# Breakout.net
KiCad netlist of a schematic drawn in Altium Designer
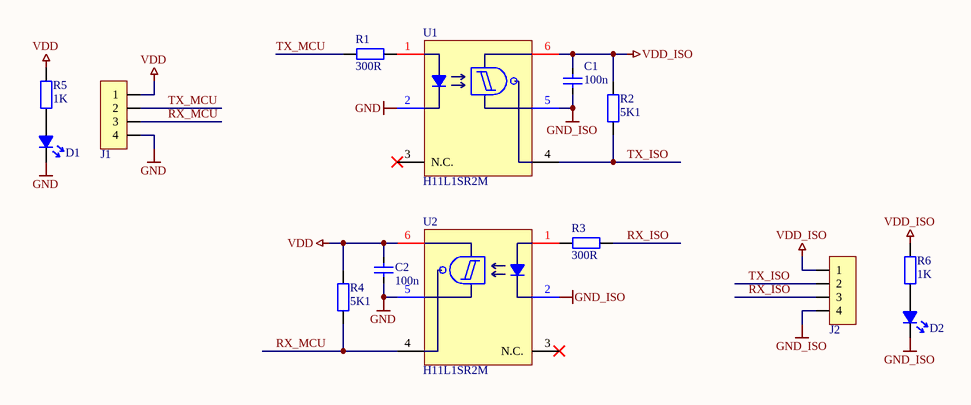
[diagram p0: Breakout.SchDoc]

(export (version "E")
  (design (tool "Eeschema 10.0.6"))
  (components
    (comp (ref "C1")
      (value "100n")
      (footprint "0805C_RF_M")
      (description "Capacitor")
      (fields (field (name "TOLERANCE") "?") (field (name "MANUFACTURER") "Generic Brand"))
      (libsource (lib "AG.Generic") (part "C"))
    )
    (comp (ref "C2")
      (value "100n")
      (footprint "0805C_RF_M")
      (description "Capacitor")
      (fields (field (name "TOLERANCE") "?") (field (name "MANUFACTURER") "Generic Brand"))
      (libsource (lib "AG.Generic") (part "C"))
    )
    (comp (ref "D1")
      (value "Unspecified")
      (footprint "0805LED_RF_M")
      (description "LED")
      (fields (field (name "MANUFACTURER") "Generic Brand"))
      (libsource (lib "AG.Generic") (part "LED"))
    )
    (comp (ref "D2")
      (value "Unspecified")
      (footprint "0805LED_RF_M")
      (description "LED")
      (fields (field (name "MANUFACTURER") "Generic Brand"))
      (libsource (lib "AG.Generic") (part "LED"))
    )
    (comp (ref "J1")
      (value "PINHDR-4P1")
      (footprint "AG.Connectors:HEADER-2.54-4P1")
      (description "Generic Pin Header 4x1")
      (libsource (lib "") (part "PINHDR-4P1_1"))
    )
    (comp (ref "J2")
      (value "PINHDR-4P1")
      (footprint "AG.Connectors:HEADER-2.54-4P1")
      (description "Generic Pin Header 4x1")
      (libsource (lib "AG.Connectors") (part "PINHDR-4P1"))
    )
    (comp (ref "R1")
      (value "300R")
      (footprint "0805R_RF_M")
      (description "Resistor")
      (fields (field (name "TOLERANCE") "?") (field (name "MANUFACTURER") "Generic Brand"))
      (libsource (lib "AG.Generic") (part "R"))
    )
    (comp (ref "R2")
      (value "5K1")
      (footprint "0805R_RF_M")
      (description "Resistor")
      (fields (field (name "TOLERANCE") "?") (field (name "MANUFACTURER") "Generic Brand"))
      (libsource (lib "AG.Generic") (part "R"))
    )
    (comp (ref "R3")
      (value "300R")
      (footprint "0805R_RF_M")
      (description "Resistor")
      (fields (field (name "TOLERANCE") "?") (field (name "MANUFACTURER") "Generic Brand"))
      (libsource (lib "AG.Generic") (part "R"))
    )
    (comp (ref "R4")
      (value "5K1")
      (footprint "0805R_RF_M")
      (description "Resistor")
      (fields (field (name "TOLERANCE") "?") (field (name "MANUFACTURER") "Generic Brand"))
      (libsource (lib "AG.Generic") (part "R"))
    )
    (comp (ref "R5")
      (value "1K")
      (footprint "0805R_RF_M")
      (description "Resistor")
      (fields (field (name "TOLERANCE") "?") (field (name "MANUFACTURER") "Generic Brand"))
      (libsource (lib "AG.Generic") (part "R"))
    )
    (comp (ref "R6")
      (value "1K")
      (footprint "0805R_RF_M")
      (description "Resistor")
      (fields (field (name "TOLERANCE") "?") (field (name "MANUFACTURER") "Generic Brand"))
      (libsource (lib "AG.Generic") (part "R"))
    )
    (comp (ref "U1")
      (value "H11L1SR2M")
      (footprint "AG.IC:H11L1SR2M_SMD-6")
      (description "OPTOISO 4.17KV OPN COLL SMD-6")
      (fields
        (field (name "MANUFACTURER") "ON Semiconductor")
        (field (name "ALTERNATIVE SUPPLIER PART NO") "753715628")
      )
      (libsource (lib "") (part "H11L1SR2M_1"))
    )
    (comp (ref "U2")
      (value "H11L1SR2M")
      (footprint "AG.IC:H11L1SR2M_SMD-6")
      (description "OPTOISO 4.17KV OPN COLL SMD-6")
      (fields
        (field (name "MANUFACTURER") "ON Semiconductor")
        (field (name "ALTERNATIVE SUPPLIER PART NO") "753715628")
      )
      (libsource (lib "AG.Discrete") (part "H11L1SR2M"))
    )
  )
  (nets
    (net (code "1") (name "/RX_ISO") (class "Default")
      (node (ref "J2") (pin "3") (pinfunction "3_3") (pintype "passive"))
      (node (ref "R3") (pin "2") (pintype "passive"))
    )
    (net (code "2") (name "/RX_MCU") (class "Default")
      (node (ref "J1") (pin "3") (pinfunction "3_3") (pintype "passive"))
      (node (ref "R4") (pin "1") (pintype "passive"))
      (node (ref "U2") (pin "4") (pinfunction "OUT_4") (pintype "passive"))
    )
    (net (code "3") (name "/TX_ISO") (class "Default")
      (node (ref "J2") (pin "2") (pinfunction "2_2") (pintype "passive"))
      (node (ref "R2") (pin "1") (pintype "passive"))
      (node (ref "U1") (pin "4") (pinfunction "OUT_4") (pintype "passive"))
    )
    (net (code "4") (name "/TX_MCU") (class "Default")
      (node (ref "J1") (pin "2") (pinfunction "2_2") (pintype "passive"))
      (node (ref "R1") (pin "1") (pintype "passive"))
    )
    (net (code "5") (name "GND") (class "Default")
      (node (ref "C2") (pin "1") (pinfunction "1_1") (pintype "passive"))
      (node (ref "D1") (pin "C") (pinfunction "C_C") (pintype "passive"))
      (node (ref "J1") (pin "4") (pinfunction "4_4") (pintype "passive"))
      (node (ref "U1") (pin "2") (pinfunction "C_2") (pintype "passive"))
      (node (ref "U2") (pin "5") (pinfunction "GND_5") (pintype "power_in"))
    )
    (net (code "6") (name "GND_ISO") (class "Default")
      (node (ref "C1") (pin "1") (pinfunction "1_1") (pintype "passive"))
      (node (ref "D2") (pin "C") (pinfunction "C_C") (pintype "passive"))
      (node (ref "J2") (pin "4") (pinfunction "4_4") (pintype "passive"))
      (node (ref "U1") (pin "5") (pinfunction "GND_5") (pintype "power_in"))
      (node (ref "U2") (pin "2") (pinfunction "C_2") (pintype "passive"))
    )
    (net (code "7") (name "Net-(D1-PadA)") (class "Default")
      (node (ref "D1") (pin "A") (pinfunction "A_A") (pintype "passive"))
      (node (ref "R5") (pin "1") (pintype "passive"))
    )
    (net (code "8") (name "Net-(D2-PadA)") (class "Default")
      (node (ref "D2") (pin "A") (pinfunction "A_A") (pintype "passive"))
      (node (ref "R6") (pin "1") (pintype "passive"))
    )
    (net (code "9") (name "Net-(U1-A)") (class "Default")
      (node (ref "R1") (pin "2") (pintype "passive"))
      (node (ref "U1") (pin "1") (pinfunction "A_1") (pintype "passive"))
    )
    (net (code "10") (name "Net-(U2-A)") (class "Default")
      (node (ref "R3") (pin "1") (pintype "passive"))
      (node (ref "U2") (pin "1") (pinfunction "A_1") (pintype "passive"))
    )
    (net (code "11") (name "VDD") (class "Default")
      (node (ref "C2") (pin "2") (pinfunction "2_2") (pintype "passive"))
      (node (ref "J1") (pin "1") (pinfunction "1_1") (pintype "passive"))
      (node (ref "R4") (pin "2") (pintype "passive"))
      (node (ref "R5") (pin "2") (pintype "passive"))
      (node (ref "U2") (pin "6") (pinfunction "VCC_6") (pintype "power_in"))
    )
    (net (code "12") (name "VDD_ISO") (class "Default")
      (node (ref "C1") (pin "2") (pinfunction "2_2") (pintype "passive"))
      (node (ref "J2") (pin "1") (pinfunction "1_1") (pintype "passive"))
      (node (ref "R2") (pin "2") (pintype "passive"))
      (node (ref "R6") (pin "2") (pintype "passive"))
      (node (ref "U1") (pin "6") (pinfunction "VCC_6") (pintype "power_in"))
    )
    (net (code "13") (name "unconnected-(U1-N.C.-Pad3)") (class "Default")
      (node (ref "U1") (pin "3") (pinfunction "N.C._3") (pintype "passive+no_connect"))
    )
    (net (code "14") (name "unconnected-(U2-N.C.-Pad3)") (class "Default")
      (node (ref "U2") (pin "3") (pinfunction "N.C._3") (pintype "passive+no_connect"))
    )
  )
)
